# TDA7052A_mono.net
KiCad netlist of a schematic drawn in EAGLE
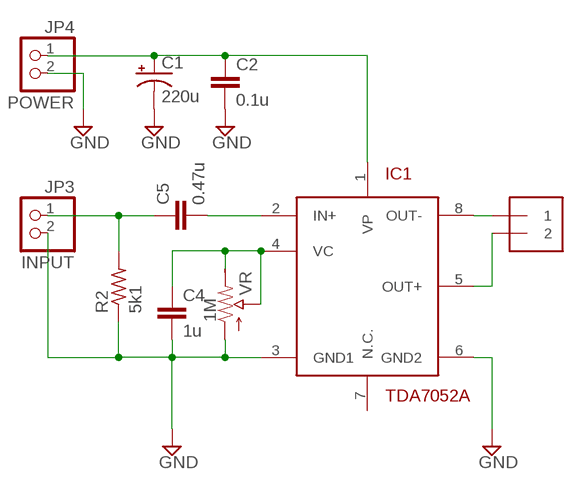
[diagram p0: schematic, sheet 1]

(export (version "E")
  (design (tool "Eeschema 10.0.6"))
  (components
    (comp (ref "C1")
      (value "220u")
      (footprint "eagle-import:CPOL-RADIAL-100UF-25V")
      (libsource (lib "eagle-import") (part "CAP_POLPTH1"))
    )
    (comp (ref "C2")
      (value "0.1u")
      (footprint "eagle-import:CAP-PTH-SMALL2")
      (libsource (lib "eagle-import") (part "CAPPTH2"))
    )
    (comp (ref "C4")
      (value "1u")
      (footprint "eagle-import:CAP-PTH-SMALL2")
      (libsource (lib "eagle-import") (part "CAPPTH2"))
    )
    (comp (ref "C5")
      (value "0.47u")
      (footprint "eagle-import:CAP-PTH-SMALL2")
      (libsource (lib "eagle-import") (part "CAPPTH2"))
    )
    (comp (ref "IC1")
      (value "TDA7052A")
      (footprint "eagle-import:DIL08")
      (libsource (lib "eagle-import") (part "TDA7052A"))
    )
    (comp (ref "JP3")
      (value "INPUT")
      (footprint "eagle-import:1X02")
      (libsource (lib "eagle-import") (part "PINHD-1X2"))
    )
    (comp (ref "JP4")
      (value "POWER")
      (footprint "eagle-import:1X02")
      (libsource (lib "eagle-import") (part "PINHD-1X2"))
    )
    (comp (ref "R2")
      (value "5k1")
      (footprint "eagle-import:0204_5")
      (libsource (lib "eagle-import") (part "R-US_0204/5"))
    )
    (comp (ref "SPEAKER")
      (value "1X2-3.5MM")
      (footprint "eagle-import:1X2-3.5MM")
      (libsource (lib "eagle-import") (part "1X2-3.5MM"))
    )
    (comp (ref "VR")
      (value "1M")
      (footprint "eagle-import:POT_ALPHA_RV16AF-20")
      (libsource (lib "eagle-import") (part "POT-RV16AF-20"))
    )
  )
  (nets
    (net (code "1") (name "GND") (class "Default")
      (node (ref "C1") (pin "2") (pinfunction "-_2") (pintype "passive"))
      (node (ref "C2") (pin "2") (pinfunction "2_2") (pintype "passive"))
      (node (ref "C4") (pin "2") (pinfunction "2_2") (pintype "passive"))
      (node (ref "IC1") (pin "3") (pinfunction "GND1_3") (pintype "power_in"))
      (node (ref "IC1") (pin "6") (pinfunction "GND2_6") (pintype "power_in"))
      (node (ref "JP3") (pin "2") (pinfunction "2_2") (pintype "passive"))
      (node (ref "JP4") (pin "2") (pinfunction "2_2") (pintype "passive"))
      (node (ref "R2") (pin "1") (pinfunction "1_1") (pintype "passive"))
      (node (ref "VR") (pin "1") (pinfunction "A_1") (pintype "passive"))
    )
    (net (code "2") (name "Net-(C1-+)") (class "Default")
      (node (ref "C1") (pin "1") (pinfunction "+_1") (pintype "passive"))
      (node (ref "C2") (pin "1") (pinfunction "1_1") (pintype "passive"))
      (node (ref "IC1") (pin "1") (pinfunction "VP_1") (pintype "power_in"))
      (node (ref "JP4") (pin "1") (pinfunction "1_1") (pintype "passive"))
    )
    (net (code "3") (name "Net-(C5-Pad1)") (class "Default")
      (node (ref "C5") (pin "1") (pinfunction "1_1") (pintype "passive"))
      (node (ref "JP3") (pin "1") (pinfunction "1_1") (pintype "passive"))
      (node (ref "R2") (pin "2") (pinfunction "2_2") (pintype "passive"))
    )
    (net (code "4") (name "Net-(IC1-IN+)") (class "Default")
      (node (ref "C5") (pin "2") (pinfunction "2_2") (pintype "passive"))
      (node (ref "IC1") (pin "2") (pinfunction "IN+_2") (pintype "input"))
    )
    (net (code "5") (name "Net-(IC1-OUT+)") (class "Default")
      (node (ref "IC1") (pin "5") (pinfunction "OUT+_5") (pintype "output"))
      (node (ref "SPEAKER") (pin "2") (pinfunction "2_2") (pintype "passive"))
    )
    (net (code "6") (name "Net-(IC1-OUT-)") (class "Default")
      (node (ref "IC1") (pin "8") (pinfunction "OUT-_8") (pintype "output"))
      (node (ref "SPEAKER") (pin "1") (pinfunction "1_1") (pintype "passive"))
    )
    (net (code "7") (name "Net-(IC1-VC)") (class "Default")
      (node (ref "C4") (pin "1") (pinfunction "1_1") (pintype "passive"))
      (node (ref "IC1") (pin "4") (pinfunction "VC_4") (pintype "output"))
      (node (ref "VR") (pin "2") (pinfunction "S_2") (pintype "passive"))
      (node (ref "VR") (pin "3") (pinfunction "E_3") (pintype "passive"))
    )
    (net (code "8") (name "unconnected-(IC1-N.C.-Pad7)") (class "Default")
      (node (ref "IC1") (pin "7") (pinfunction "N.C._7") (pintype "no_connect"))
    )
  )
)
